# amplifier.net
KiCad netlist of a schematic drawn in EAGLE
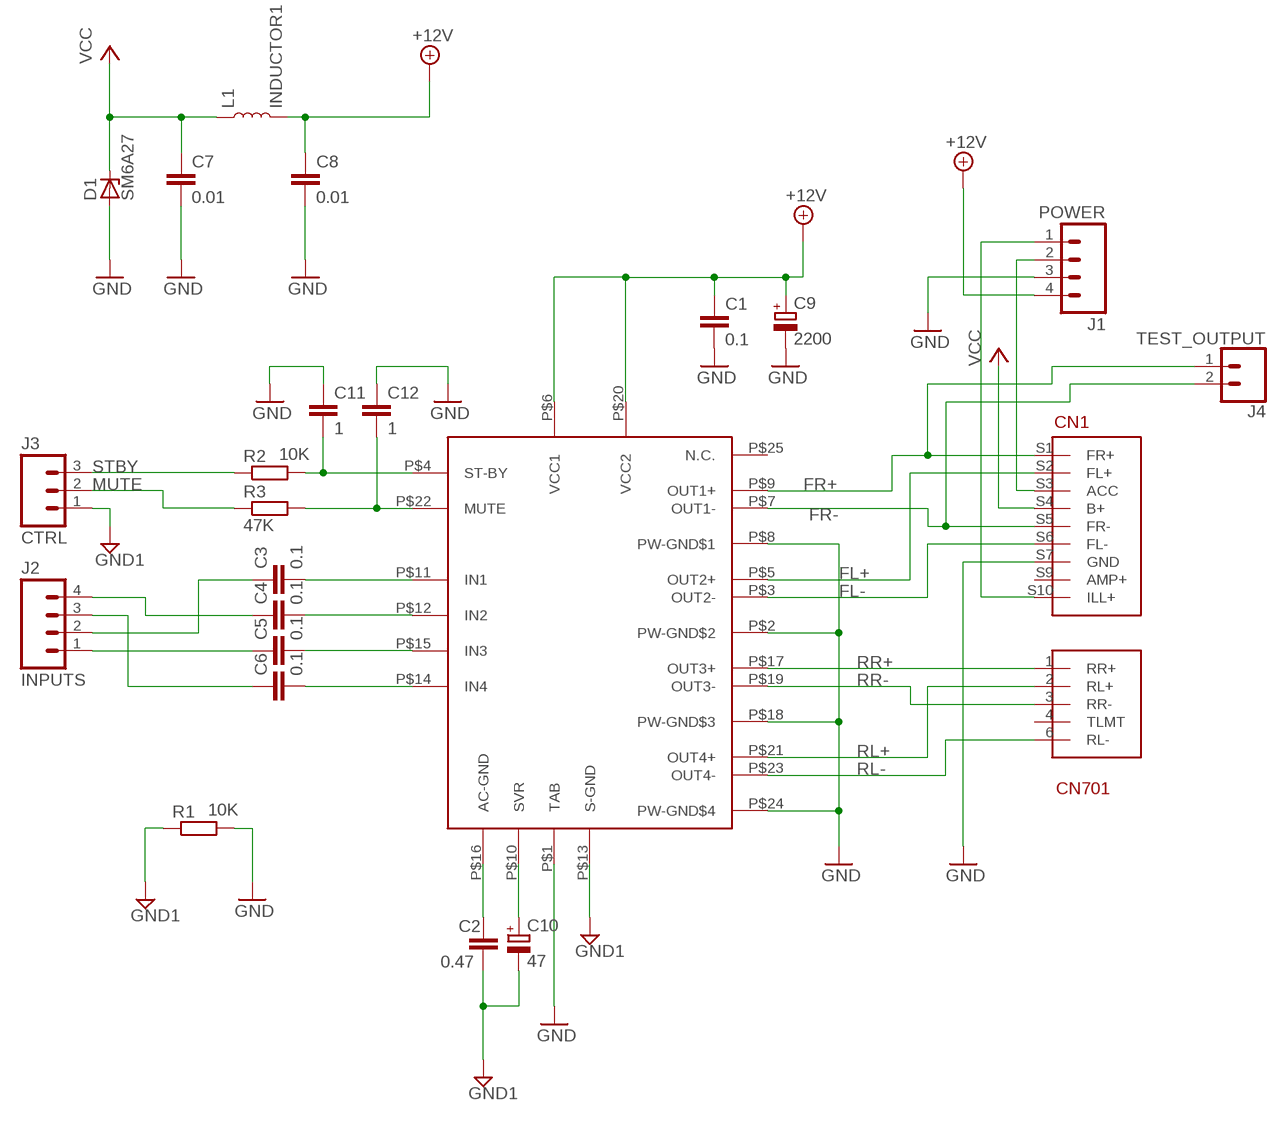
[diagram p0: schematic, sheet 1]

(export (version "E")
  (design (tool "Eeschema 10.0.6"))
  (components
    (comp (ref "C1")
      (value "0.1")
      (footprint "eagle-import:C1206")
      (libsource (lib "eagle-import") (part "C-EUC1206"))
    )
    (comp (ref "C2")
      (value "0.47")
      (footprint "eagle-import:C1206")
      (libsource (lib "eagle-import") (part "C-EUC1206"))
    )
    (comp (ref "C3")
      (value "0.1")
      (footprint "eagle-import:C1206")
      (libsource (lib "eagle-import") (part "C-EUC1206"))
    )
    (comp (ref "C4")
      (value "0.1")
      (footprint "eagle-import:C1206")
      (libsource (lib "eagle-import") (part "C-EUC1206"))
    )
    (comp (ref "C5")
      (value "0.1")
      (footprint "eagle-import:C1206")
      (libsource (lib "eagle-import") (part "C-EUC1206"))
    )
    (comp (ref "C6")
      (value "0.1")
      (footprint "eagle-import:C1206")
      (libsource (lib "eagle-import") (part "C-EUC1206"))
    )
    (comp (ref "C7")
      (value "0.01")
      (footprint "eagle-import:C1206")
      (libsource (lib "eagle-import") (part "C-EUC1206"))
    )
    (comp (ref "C8")
      (value "0.01")
      (footprint "eagle-import:C1206")
      (libsource (lib "eagle-import") (part "C-EUC1206"))
    )
    (comp (ref "C9")
      (value "2200")
      (footprint "eagle-import:E5-10,5")
      (libsource (lib "eagle-import") (part "CPOL-EUE5-10.5"))
    )
    (comp (ref "C10")
      (value "47")
      (footprint "eagle-import:E5-4")
      (libsource (lib "eagle-import") (part "CPOL-EUE5-4"))
    )
    (comp (ref "C11")
      (value "1")
      (footprint "eagle-import:C1206")
      (libsource (lib "eagle-import") (part "C-EUC1206"))
    )
    (comp (ref "C12")
      (value "1")
      (footprint "eagle-import:C1206")
      (libsource (lib "eagle-import") (part "C-EUC1206"))
    )
    (comp (ref "CN1")
      (value "CN701")
      (footprint "eagle-import:CN701")
      (libsource (lib "eagle-import") (part "CN701"))
    )
    (comp (ref "D1")
      (value "SM6A27")
      (footprint "eagle-import:DO-218AB")
      (libsource (lib "eagle-import") (part "SM6A27"))
    )
    (comp (ref "J1")
      (value "POWER")
      (footprint "eagle-import:1X04_LOCK_LONGPADS")
      (libsource (lib "eagle-import") (part "M04LOCK_LONGPADS"))
    )
    (comp (ref "J2")
      (value "INPUTS")
      (footprint "eagle-import:1X04_LOCK_LONGPADS")
      (libsource (lib "eagle-import") (part "M04LOCK_LONGPADS"))
    )
    (comp (ref "J3")
      (value "CTRL")
      (footprint "eagle-import:1X03_LOCK_LONGPADS@1")
      (libsource (lib "eagle-import") (part "M03LOCK_LONGPADS"))
    )
    (comp (ref "J4")
      (value "TEST_OUTPUT")
      (footprint "eagle-import:1X02_LOCK_LONGPADS")
      (libsource (lib "eagle-import") (part "CONN_02LOCK_LONGPADS"))
    )
    (comp (ref "L1")
      (value "INDUCTOR1")
      (footprint "eagle-import:INDUCTOR1")
      (libsource (lib "eagle-import") (part "INDUCTOR1"))
    )
    (comp (ref "R1")
      (value "10K")
      (footprint "eagle-import:M1206")
      (libsource (lib "eagle-import") (part "R-EU_M1206"))
    )
    (comp (ref "R2")
      (value "10K")
      (footprint "eagle-import:M1206")
      (libsource (lib "eagle-import") (part "R-EU_M1206"))
    )
    (comp (ref "R3")
      (value "47K")
      (footprint "eagle-import:M1206")
      (libsource (lib "eagle-import") (part "R-EU_M1206"))
    )
    (comp (ref "U$1")
      (value "TDA7386")
      (footprint "eagle-import:TDA7386")
      (libsource (lib "eagle-import") (part "TDA7386"))
    )
  )
  (nets
    (net (code "1") (name "+12V") (class "Default")
      (node (ref "C1") (pin "1") (pinfunction "1_1") (pintype "passive"))
      (node (ref "C8") (pin "1") (pinfunction "1_1") (pintype "passive"))
      (node (ref "C9") (pin "+") (pinfunction "+_+") (pintype "passive"))
      (node (ref "J1") (pin "4") (pinfunction "4_4") (pintype "passive"))
      (node (ref "L1") (pin "2") (pinfunction "2_2") (pintype "passive"))
      (node (ref "U$1") (pin "P$20") (pinfunction "VCC2_P$20") (pintype "bidirectional"))
      (node (ref "U$1") (pin "P$6") (pinfunction "VCC1_P$6") (pintype "bidirectional"))
    )
    (net (code "2") (name "/FL+") (class "Default")
      (node (ref "CN1") (pin "S2") (pinfunction "FL+_S2") (pintype "bidirectional"))
      (node (ref "U$1") (pin "P$5") (pinfunction "OUT2+_P$5") (pintype "bidirectional"))
    )
    (net (code "3") (name "/FL-") (class "Default")
      (node (ref "CN1") (pin "S6") (pinfunction "FL-_S6") (pintype "bidirectional"))
      (node (ref "U$1") (pin "P$3") (pinfunction "OUT2-_P$3") (pintype "bidirectional"))
    )
    (net (code "4") (name "/FR+") (class "Default")
      (node (ref "CN1") (pin "S1") (pinfunction "FR+_S1") (pintype "bidirectional"))
      (node (ref "J4") (pin "1") (pinfunction "1_1") (pintype "passive"))
      (node (ref "U$1") (pin "P$9") (pinfunction "OUT1+_P$9") (pintype "bidirectional"))
    )
    (net (code "5") (name "/FR-") (class "Default")
      (node (ref "CN1") (pin "S5") (pinfunction "FR-_S5") (pintype "bidirectional"))
      (node (ref "J4") (pin "2") (pinfunction "2_2") (pintype "passive"))
      (node (ref "U$1") (pin "P$7") (pinfunction "OUT1-_P$7") (pintype "bidirectional"))
    )
    (net (code "6") (name "/MUTE") (class "Default")
      (node (ref "J3") (pin "2") (pinfunction "2_2") (pintype "passive"))
      (node (ref "R3") (pin "1") (pinfunction "1_1") (pintype "passive"))
    )
    (net (code "7") (name "/RL+") (class "Default")
      (node (ref "CN1") (pin "2") (pinfunction "RL+_2") (pintype "bidirectional"))
      (node (ref "U$1") (pin "P$21") (pinfunction "OUT4+_P$21") (pintype "bidirectional"))
    )
    (net (code "8") (name "/RL-") (class "Default")
      (node (ref "CN1") (pin "6") (pinfunction "RL-_6") (pintype "bidirectional"))
      (node (ref "U$1") (pin "P$23") (pinfunction "OUT4-_P$23") (pintype "bidirectional"))
    )
    (net (code "9") (name "/RR+") (class "Default")
      (node (ref "CN1") (pin "1") (pinfunction "RR+_1") (pintype "bidirectional"))
      (node (ref "U$1") (pin "P$17") (pinfunction "OUT3+_P$17") (pintype "bidirectional"))
    )
    (net (code "10") (name "/RR-") (class "Default")
      (node (ref "CN1") (pin "3") (pinfunction "RR-_3") (pintype "bidirectional"))
      (node (ref "U$1") (pin "P$19") (pinfunction "OUT3-_P$19") (pintype "bidirectional"))
    )
    (net (code "11") (name "/STBY") (class "Default")
      (node (ref "J3") (pin "3") (pinfunction "3_3") (pintype "passive"))
      (node (ref "R2") (pin "1") (pinfunction "1_1") (pintype "passive"))
    )
    (net (code "12") (name "GND") (class "Default")
      (node (ref "C1") (pin "2") (pinfunction "2_2") (pintype "passive"))
      (node (ref "C11") (pin "1") (pinfunction "1_1") (pintype "passive"))
      (node (ref "C12") (pin "1") (pinfunction "1_1") (pintype "passive"))
      (node (ref "C7") (pin "2") (pinfunction "2_2") (pintype "passive"))
      (node (ref "C8") (pin "2") (pinfunction "2_2") (pintype "passive"))
      (node (ref "C9") (pin "-") (pinfunction "-_-") (pintype "passive"))
      (node (ref "CN1") (pin "S7") (pinfunction "GND_S7") (pintype "bidirectional"))
      (node (ref "D1") (pin "A") (pinfunction "A_A") (pintype "passive"))
      (node (ref "J1") (pin "3") (pinfunction "3_3") (pintype "passive"))
      (node (ref "R1") (pin "2") (pinfunction "2_2") (pintype "passive"))
      (node (ref "U$1") (pin "P$1") (pinfunction "TAB_P$1") (pintype "bidirectional"))
      (node (ref "U$1") (pin "P$18") (pinfunction "PW-GND$3_P$18") (pintype "bidirectional"))
      (node (ref "U$1") (pin "P$2") (pinfunction "PW-GND$2_P$2") (pintype "bidirectional"))
      (node (ref "U$1") (pin "P$24") (pinfunction "PW-GND$4_P$24") (pintype "bidirectional"))
      (node (ref "U$1") (pin "P$8") (pinfunction "PW-GND$1_P$8") (pintype "bidirectional"))
    )
    (net (code "13") (name "GND1") (class "Default")
      (node (ref "C10") (pin "-") (pinfunction "-_-") (pintype "passive"))
      (node (ref "C2") (pin "2") (pinfunction "2_2") (pintype "passive"))
      (node (ref "J3") (pin "1") (pinfunction "1_1") (pintype "passive"))
      (node (ref "R1") (pin "1") (pinfunction "1_1") (pintype "passive"))
      (node (ref "U$1") (pin "P$13") (pinfunction "S-GND_P$13") (pintype "bidirectional"))
    )
    (net (code "14") (name "Net-(C3-Pad1)") (class "Default")
      (node (ref "C3") (pin "1") (pinfunction "1_1") (pintype "passive"))
      (node (ref "J2") (pin "2") (pinfunction "2_2") (pintype "passive"))
    )
    (net (code "15") (name "Net-(C4-Pad1)") (class "Default")
      (node (ref "C4") (pin "1") (pinfunction "1_1") (pintype "passive"))
      (node (ref "J2") (pin "4") (pinfunction "4_4") (pintype "passive"))
    )
    (net (code "16") (name "Net-(C5-Pad1)") (class "Default")
      (node (ref "C5") (pin "1") (pinfunction "1_1") (pintype "passive"))
      (node (ref "J2") (pin "1") (pinfunction "1_1") (pintype "passive"))
    )
    (net (code "17") (name "Net-(C6-Pad1)") (class "Default")
      (node (ref "C6") (pin "1") (pinfunction "1_1") (pintype "passive"))
      (node (ref "J2") (pin "3") (pinfunction "3_3") (pintype "passive"))
    )
    (net (code "18") (name "Net-(CN1-ACC)") (class "Default")
      (node (ref "CN1") (pin "S3") (pinfunction "ACC_S3") (pintype "bidirectional"))
      (node (ref "J1") (pin "2") (pinfunction "2_2") (pintype "passive"))
    )
    (net (code "19") (name "Net-(CN1-ILL+)") (class "Default")
      (node (ref "CN1") (pin "S10") (pinfunction "ILL+_S10") (pintype "bidirectional"))
      (node (ref "J1") (pin "1") (pinfunction "1_1") (pintype "passive"))
    )
    (net (code "20") (name "Net-(U$1-AC-GND)") (class "Default")
      (node (ref "C2") (pin "1") (pinfunction "1_1") (pintype "passive"))
      (node (ref "U$1") (pin "P$16") (pinfunction "AC-GND_P$16") (pintype "bidirectional"))
    )
    (net (code "21") (name "Net-(U$1-IN1)") (class "Default")
      (node (ref "C3") (pin "2") (pinfunction "2_2") (pintype "passive"))
      (node (ref "U$1") (pin "P$11") (pinfunction "IN1_P$11") (pintype "bidirectional"))
    )
    (net (code "22") (name "Net-(U$1-IN2)") (class "Default")
      (node (ref "C4") (pin "2") (pinfunction "2_2") (pintype "passive"))
      (node (ref "U$1") (pin "P$12") (pinfunction "IN2_P$12") (pintype "bidirectional"))
    )
    (net (code "23") (name "Net-(U$1-IN3)") (class "Default")
      (node (ref "C5") (pin "2") (pinfunction "2_2") (pintype "passive"))
      (node (ref "U$1") (pin "P$15") (pinfunction "IN3_P$15") (pintype "bidirectional"))
    )
    (net (code "24") (name "Net-(U$1-IN4)") (class "Default")
      (node (ref "C6") (pin "2") (pinfunction "2_2") (pintype "passive"))
      (node (ref "U$1") (pin "P$14") (pinfunction "IN4_P$14") (pintype "bidirectional"))
    )
    (net (code "25") (name "Net-(U$1-MUTE)") (class "Default")
      (node (ref "C12") (pin "2") (pinfunction "2_2") (pintype "passive"))
      (node (ref "R3") (pin "2") (pinfunction "2_2") (pintype "passive"))
      (node (ref "U$1") (pin "P$22") (pinfunction "MUTE_P$22") (pintype "bidirectional"))
    )
    (net (code "26") (name "Net-(U$1-ST-BY)") (class "Default")
      (node (ref "C11") (pin "2") (pinfunction "2_2") (pintype "passive"))
      (node (ref "R2") (pin "2") (pinfunction "2_2") (pintype "passive"))
      (node (ref "U$1") (pin "P$4") (pinfunction "ST-BY_P$4") (pintype "bidirectional"))
    )
    (net (code "27") (name "Net-(U$1-SVR)") (class "Default")
      (node (ref "C10") (pin "+") (pinfunction "+_+") (pintype "passive"))
      (node (ref "U$1") (pin "P$10") (pinfunction "SVR_P$10") (pintype "bidirectional"))
    )
    (net (code "28") (name "VCC") (class "Default")
      (node (ref "C7") (pin "1") (pinfunction "1_1") (pintype "passive"))
      (node (ref "CN1") (pin "S4") (pinfunction "B+_S4") (pintype "bidirectional"))
      (node (ref "D1") (pin "C") (pinfunction "C_C") (pintype "passive"))
      (node (ref "L1") (pin "1") (pinfunction "1_1") (pintype "passive"))
    )
    (net (code "29") (name "unconnected-(CN1-AMP+-PadS9)") (class "Default")
      (node (ref "CN1") (pin "S9") (pinfunction "AMP+_S9") (pintype "bidirectional"))
    )
    (net (code "30") (name "unconnected-(CN1-TLMT-Pad4)") (class "Default")
      (node (ref "CN1") (pin "4") (pinfunction "TLMT_4") (pintype "bidirectional"))
    )
    (net (code "31") (name "unconnected-(U$1-N.C.-PadP$25)") (class "Default")
      (node (ref "U$1") (pin "P$25") (pinfunction "N.C._P$25") (pintype "bidirectional"))
    )
  )
)
